# SHASwitchOutput.net
KiCad netlist of a schematic drawn in EAGLE
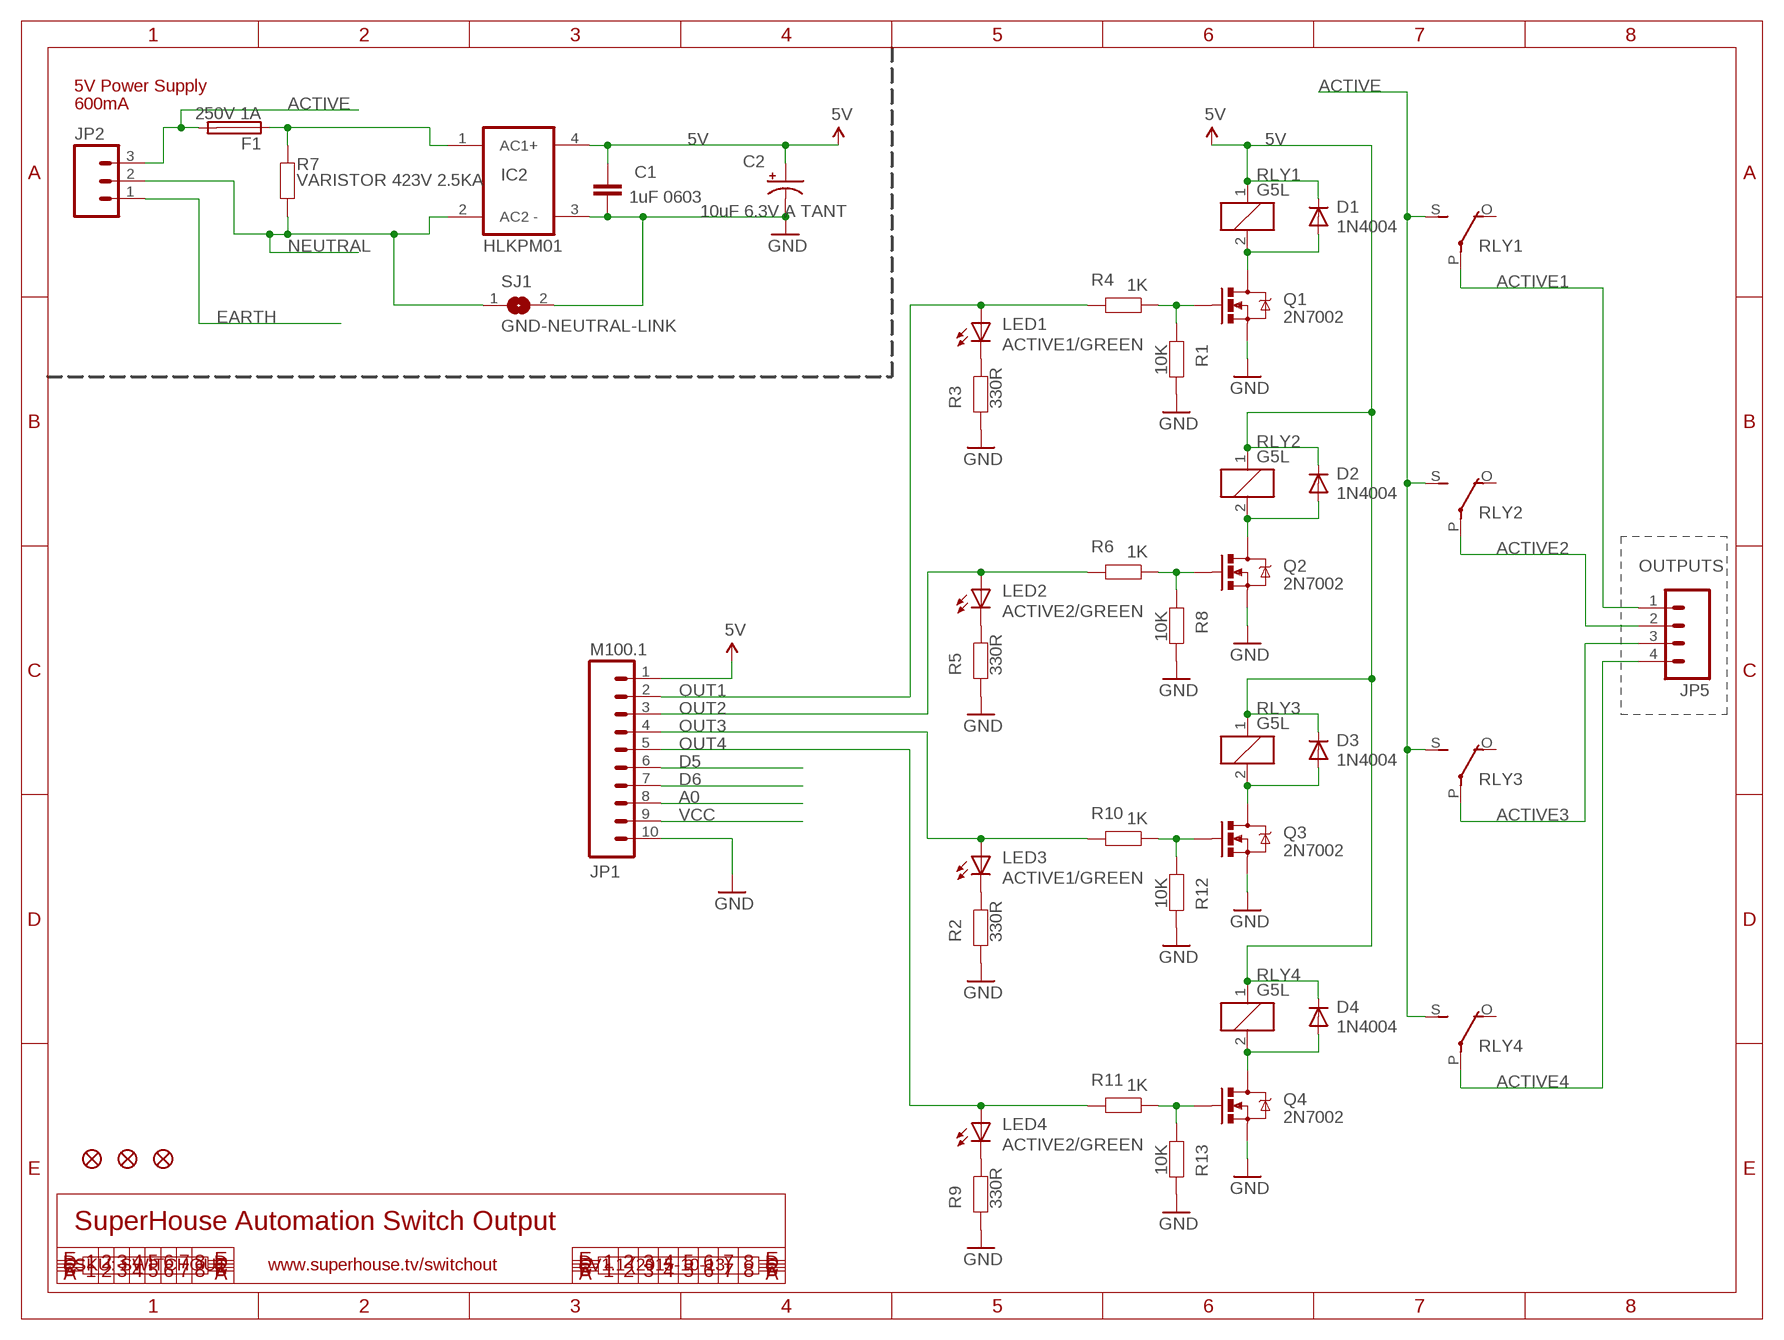
[diagram p0: schematic, sheet 1]

(export (version "E")
  (design (tool "Eeschema 10.0.6"))
  (components
    (comp (ref "C1")
      (value "1uF 0603")
      (footprint "eagle-import:0603@1")
      (libsource (lib "eagle-import") (part "CAP0603"))
    )
    (comp (ref "C2")
      (value "10uF 6.3V A TANT")
      (footprint "eagle-import:EIA3216")
      (libsource (lib "eagle-import") (part "CAP_POL1206"))
    )
    (comp (ref "D1")
      (value "1N4004")
      (footprint "eagle-import:SMB-DIODE")
      (libsource (lib "eagle-import") (part "DIODESMB"))
    )
    (comp (ref "D2")
      (value "1N4004")
      (footprint "eagle-import:SMB-DIODE")
      (libsource (lib "eagle-import") (part "DIODESMB"))
    )
    (comp (ref "D3")
      (value "1N4004")
      (footprint "eagle-import:SMB-DIODE")
      (libsource (lib "eagle-import") (part "DIODESMB"))
    )
    (comp (ref "D4")
      (value "1N4004")
      (footprint "eagle-import:SMB-DIODE")
      (libsource (lib "eagle-import") (part "DIODESMB"))
    )
    (comp (ref "F1")
      (value "250V 1A")
      (footprint "eagle-import:PICOFUSE-V")
      (libsource (lib "eagle-import") (part "PICOFUSEV"))
    )
    (comp (ref "FID1")
      (value "FIDUCIAL1X2.5")
      (footprint "eagle-import:FIDUCIAL-1X2.5")
      (libsource (lib "eagle-import") (part "FIDUCIAL1X2.5"))
    )
    (comp (ref "FID2")
      (value "FIDUCIAL1X2.5")
      (footprint "eagle-import:FIDUCIAL-1X2.5")
      (libsource (lib "eagle-import") (part "FIDUCIAL1X2.5"))
    )
    (comp (ref "FID3")
      (value "FIDUCIAL1X2.5")
      (footprint "eagle-import:FIDUCIAL-1X2.5")
      (libsource (lib "eagle-import") (part "FIDUCIAL1X2.5"))
    )
    (comp (ref "IC2")
      (value "HLKPM01")
      (footprint "eagle-import:HLKPM01")
      (libsource (lib "eagle-import") (part "HLKPM01"))
    )
    (comp (ref "JP1")
      (value "M100.1")
      (footprint "eagle-import:1X10")
      (libsource (lib "eagle-import") (part "M100.1"))
    )
    (comp (ref "JP2")
      (value "M035MM")
      (footprint "eagle-import:SCREWTERMINAL-5MM-3")
      (libsource (lib "eagle-import") (part "M035MM"))
    )
    (comp (ref "JP5")
      (value "M045MM")
      (footprint "eagle-import:SCREWTERMINAL-5MM-4")
      (libsource (lib "eagle-import") (part "M045MM"))
    )
    (comp (ref "LED1")
      (value "ACTIVE1/GREEN")
      (footprint "eagle-import:LED-0603")
      (libsource (lib "eagle-import") (part "LED0603"))
    )
    (comp (ref "LED2")
      (value "ACTIVE2/GREEN")
      (footprint "eagle-import:LED-0603")
      (libsource (lib "eagle-import") (part "LED0603"))
    )
    (comp (ref "LED3")
      (value "ACTIVE1/GREEN")
      (footprint "eagle-import:LED-0603")
      (libsource (lib "eagle-import") (part "LED0603"))
    )
    (comp (ref "LED4")
      (value "ACTIVE2/GREEN")
      (footprint "eagle-import:LED-0603")
      (libsource (lib "eagle-import") (part "LED0603"))
    )
    (comp (ref "Q1")
      (value "2N7002")
      (footprint "eagle-import:SOT23-3")
      (libsource (lib "eagle-import") (part "MOSFET-NCHANNELSMD"))
    )
    (comp (ref "Q2")
      (value "2N7002")
      (footprint "eagle-import:SOT23-3")
      (libsource (lib "eagle-import") (part "MOSFET-NCHANNELSMD"))
    )
    (comp (ref "Q3")
      (value "2N7002")
      (footprint "eagle-import:SOT23-3")
      (libsource (lib "eagle-import") (part "MOSFET-NCHANNELSMD"))
    )
    (comp (ref "Q4")
      (value "2N7002")
      (footprint "eagle-import:SOT23-3")
      (libsource (lib "eagle-import") (part "MOSFET-NCHANNELSMD"))
    )
    (comp (ref "R1")
      (value "10K")
      (footprint "eagle-import:0603")
      (libsource (lib "eagle-import") (part "RESISTOR0603"))
    )
    (comp (ref "R2")
      (value "330R")
      (footprint "eagle-import:0603")
      (libsource (lib "eagle-import") (part "RESISTOR0603"))
    )
    (comp (ref "R3")
      (value "330R")
      (footprint "eagle-import:0603")
      (libsource (lib "eagle-import") (part "RESISTOR0603"))
    )
    (comp (ref "R4")
      (value "1K")
      (footprint "eagle-import:0603")
      (libsource (lib "eagle-import") (part "RESISTOR0603"))
    )
    (comp (ref "R5")
      (value "330R")
      (footprint "eagle-import:0603")
      (libsource (lib "eagle-import") (part "RESISTOR0603"))
    )
    (comp (ref "R6")
      (value "1K")
      (footprint "eagle-import:0603")
      (libsource (lib "eagle-import") (part "RESISTOR0603"))
    )
    (comp (ref "R7")
      (value "VARISTOR 423V 2.5KA")
      (footprint "eagle-import:AXIAL-0.3")
      (libsource (lib "eagle-import") (part "freetronics-master-v1.1_RESISTORPTH1"))
    )
    (comp (ref "R8")
      (value "10K")
      (footprint "eagle-import:0603")
      (libsource (lib "eagle-import") (part "RESISTOR0603"))
    )
    (comp (ref "R9")
      (value "330R")
      (footprint "eagle-import:0603")
      (libsource (lib "eagle-import") (part "RESISTOR0603"))
    )
    (comp (ref "R10")
      (value "1K")
      (footprint "eagle-import:0603")
      (libsource (lib "eagle-import") (part "RESISTOR0603"))
    )
    (comp (ref "R11")
      (value "1K")
      (footprint "eagle-import:0603")
      (libsource (lib "eagle-import") (part "RESISTOR0603"))
    )
    (comp (ref "R12")
      (value "10K")
      (footprint "eagle-import:0603")
      (libsource (lib "eagle-import") (part "RESISTOR0603"))
    )
    (comp (ref "R13")
      (value "10K")
      (footprint "eagle-import:0603")
      (libsource (lib "eagle-import") (part "RESISTOR0603"))
    )
    (comp (ref "RLY1")
      (value "G5L")
      (footprint "eagle-import:G5LE")
      (libsource (lib "eagle-import") (part "G5L"))
    )
    (comp (ref "RLY2")
      (value "G5L")
      (footprint "eagle-import:G5LE")
      (libsource (lib "eagle-import") (part "G5L"))
    )
    (comp (ref "RLY3")
      (value "G5L")
      (footprint "eagle-import:G5LE")
      (libsource (lib "eagle-import") (part "G5L"))
    )
    (comp (ref "RLY4")
      (value "G5L")
      (footprint "eagle-import:G5LE")
      (libsource (lib "eagle-import") (part "G5L"))
    )
    (comp (ref "SJ1")
      (value "GND-NEUTRAL-LINK")
      (footprint "eagle-import:SJ")
      (libsource (lib "eagle-import") (part "SJN"))
    )
  )
  (nets
    (net (code "1") (name "/A0") (class "Default")
      (node (ref "JP1") (pin "8") (pinfunction "8_8") (pintype "passive"))
    )
    (net (code "2") (name "/ACTIVE") (class "Default")
      (node (ref "F1") (pin "2") (pinfunction "2_2") (pintype "passive"))
      (node (ref "JP2") (pin "3") (pinfunction "3_3") (pintype "passive"))
      (node (ref "RLY1") (pin "S") (pinfunction "S_S") (pintype "passive"))
      (node (ref "RLY2") (pin "S") (pinfunction "S_S") (pintype "passive"))
      (node (ref "RLY3") (pin "S") (pinfunction "S_S") (pintype "passive"))
      (node (ref "RLY4") (pin "S") (pinfunction "S_S") (pintype "passive"))
    )
    (net (code "3") (name "/ACTIVE1") (class "Default")
      (node (ref "JP5") (pin "1") (pinfunction "1_1") (pintype "passive"))
      (node (ref "RLY1") (pin "P") (pinfunction "P_P") (pintype "passive"))
    )
    (net (code "4") (name "/ACTIVE2") (class "Default")
      (node (ref "JP5") (pin "2") (pinfunction "2_2") (pintype "passive"))
      (node (ref "RLY2") (pin "P") (pinfunction "P_P") (pintype "passive"))
    )
    (net (code "5") (name "/ACTIVE3") (class "Default")
      (node (ref "JP5") (pin "3") (pinfunction "3_3") (pintype "passive"))
      (node (ref "RLY3") (pin "P") (pinfunction "P_P") (pintype "passive"))
    )
    (net (code "6") (name "/ACTIVE4") (class "Default")
      (node (ref "JP5") (pin "4") (pinfunction "4_4") (pintype "passive"))
      (node (ref "RLY4") (pin "P") (pinfunction "P_P") (pintype "passive"))
    )
    (net (code "7") (name "/D5") (class "Default")
      (node (ref "JP1") (pin "6") (pinfunction "6_6") (pintype "passive"))
    )
    (net (code "8") (name "/D6") (class "Default")
      (node (ref "JP1") (pin "7") (pinfunction "7_7") (pintype "passive"))
    )
    (net (code "9") (name "/EARTH") (class "Default")
      (node (ref "JP2") (pin "1") (pinfunction "1_1") (pintype "passive"))
    )
    (net (code "10") (name "/NEUTRAL") (class "Default")
      (node (ref "IC2") (pin "2") (pinfunction "AC2_2") (pintype "bidirectional"))
      (node (ref "JP2") (pin "2") (pinfunction "2_2") (pintype "passive"))
      (node (ref "R7") (pin "P$1") (pinfunction "1_P$1") (pintype "passive"))
      (node (ref "SJ1") (pin "1") (pinfunction "1_1") (pintype "passive"))
    )
    (net (code "11") (name "/OUT1") (class "Default")
      (node (ref "JP1") (pin "2") (pinfunction "2_2") (pintype "passive"))
      (node (ref "LED1") (pin "A") (pinfunction "A_A") (pintype "passive"))
      (node (ref "R4") (pin "2") (pinfunction "2_2") (pintype "passive"))
    )
    (net (code "12") (name "/OUT2") (class "Default")
      (node (ref "JP1") (pin "3") (pinfunction "3_3") (pintype "passive"))
      (node (ref "LED2") (pin "A") (pinfunction "A_A") (pintype "passive"))
      (node (ref "R6") (pin "2") (pinfunction "2_2") (pintype "passive"))
    )
    (net (code "13") (name "/OUT3") (class "Default")
      (node (ref "JP1") (pin "4") (pinfunction "4_4") (pintype "passive"))
      (node (ref "LED3") (pin "A") (pinfunction "A_A") (pintype "passive"))
      (node (ref "R10") (pin "2") (pinfunction "2_2") (pintype "passive"))
    )
    (net (code "14") (name "/OUT4") (class "Default")
      (node (ref "JP1") (pin "5") (pinfunction "5_5") (pintype "passive"))
      (node (ref "LED4") (pin "A") (pinfunction "A_A") (pintype "passive"))
      (node (ref "R11") (pin "2") (pinfunction "2_2") (pintype "passive"))
    )
    (net (code "15") (name "/VCC") (class "Default")
      (node (ref "JP1") (pin "9") (pinfunction "9_9") (pintype "passive"))
    )
    (net (code "16") (name "5V") (class "Default")
      (node (ref "C1") (pin "1") (pinfunction "1_1") (pintype "passive"))
      (node (ref "C2") (pin "A") (pinfunction "+_A") (pintype "passive"))
      (node (ref "D1") (pin "C") (pinfunction "C_C") (pintype "passive"))
      (node (ref "D2") (pin "C") (pinfunction "C_C") (pintype "passive"))
      (node (ref "D3") (pin "C") (pinfunction "C_C") (pintype "passive"))
      (node (ref "D4") (pin "C") (pinfunction "C_C") (pintype "passive"))
      (node (ref "IC2") (pin "4") (pinfunction "+_4") (pintype "bidirectional"))
      (node (ref "JP1") (pin "1") (pinfunction "1_1") (pintype "passive"))
      (node (ref "RLY1") (pin "1") (pinfunction "1_1") (pintype "passive"))
      (node (ref "RLY2") (pin "1") (pinfunction "1_1") (pintype "passive"))
      (node (ref "RLY3") (pin "1") (pinfunction "1_1") (pintype "passive"))
      (node (ref "RLY4") (pin "1") (pinfunction "1_1") (pintype "passive"))
    )
    (net (code "17") (name "GND") (class "Default")
      (node (ref "C1") (pin "2") (pinfunction "2_2") (pintype "passive"))
      (node (ref "C2") (pin "C") (pinfunction "-_C") (pintype "passive"))
      (node (ref "IC2") (pin "3") (pinfunction "-_3") (pintype "bidirectional"))
      (node (ref "JP1") (pin "10") (pinfunction "10_10") (pintype "passive"))
      (node (ref "Q1") (pin "2") (pinfunction "S_2") (pintype "passive"))
      (node (ref "Q2") (pin "2") (pinfunction "S_2") (pintype "passive"))
      (node (ref "Q3") (pin "2") (pinfunction "S_2") (pintype "passive"))
      (node (ref "Q4") (pin "2") (pinfunction "S_2") (pintype "passive"))
      (node (ref "R1") (pin "2") (pinfunction "2_2") (pintype "passive"))
      (node (ref "R12") (pin "2") (pinfunction "2_2") (pintype "passive"))
      (node (ref "R13") (pin "2") (pinfunction "2_2") (pintype "passive"))
      (node (ref "R2") (pin "1") (pinfunction "1_1") (pintype "passive"))
      (node (ref "R3") (pin "1") (pinfunction "1_1") (pintype "passive"))
      (node (ref "R5") (pin "1") (pinfunction "1_1") (pintype "passive"))
      (node (ref "R8") (pin "2") (pinfunction "2_2") (pintype "passive"))
      (node (ref "R9") (pin "1") (pinfunction "1_1") (pintype "passive"))
      (node (ref "SJ1") (pin "2") (pinfunction "2_2") (pintype "passive"))
    )
    (net (code "18") (name "Net-(IC2-AC1)") (class "Default")
      (node (ref "F1") (pin "1") (pinfunction "1_1") (pintype "passive"))
      (node (ref "IC2") (pin "1") (pinfunction "AC1_1") (pintype "bidirectional"))
      (node (ref "R7") (pin "P$2") (pinfunction "2_P$2") (pintype "passive"))
    )
    (net (code "19") (name "Net-(LED1-PadC)") (class "Default")
      (node (ref "LED1") (pin "C") (pinfunction "C_C") (pintype "passive"))
      (node (ref "R3") (pin "2") (pinfunction "2_2") (pintype "passive"))
    )
    (net (code "20") (name "Net-(LED2-PadC)") (class "Default")
      (node (ref "LED2") (pin "C") (pinfunction "C_C") (pintype "passive"))
      (node (ref "R5") (pin "2") (pinfunction "2_2") (pintype "passive"))
    )
    (net (code "21") (name "Net-(LED3-PadC)") (class "Default")
      (node (ref "LED3") (pin "C") (pinfunction "C_C") (pintype "passive"))
      (node (ref "R2") (pin "2") (pinfunction "2_2") (pintype "passive"))
    )
    (net (code "22") (name "Net-(LED4-PadC)") (class "Default")
      (node (ref "LED4") (pin "C") (pinfunction "C_C") (pintype "passive"))
      (node (ref "R9") (pin "2") (pinfunction "2_2") (pintype "passive"))
    )
    (net (code "23") (name "Net-(Q1-D)") (class "Default")
      (node (ref "D1") (pin "A") (pinfunction "A_A") (pintype "passive"))
      (node (ref "Q1") (pin "3") (pinfunction "D_3") (pintype "passive"))
      (node (ref "RLY1") (pin "2") (pinfunction "2_2") (pintype "passive"))
    )
    (net (code "24") (name "Net-(Q1-G)") (class "Default")
      (node (ref "Q1") (pin "1") (pinfunction "G_1") (pintype "passive"))
      (node (ref "R1") (pin "1") (pinfunction "1_1") (pintype "passive"))
      (node (ref "R4") (pin "1") (pinfunction "1_1") (pintype "passive"))
    )
    (net (code "25") (name "Net-(Q2-D)") (class "Default")
      (node (ref "D2") (pin "A") (pinfunction "A_A") (pintype "passive"))
      (node (ref "Q2") (pin "3") (pinfunction "D_3") (pintype "passive"))
      (node (ref "RLY2") (pin "2") (pinfunction "2_2") (pintype "passive"))
    )
    (net (code "26") (name "Net-(Q2-G)") (class "Default")
      (node (ref "Q2") (pin "1") (pinfunction "G_1") (pintype "passive"))
      (node (ref "R6") (pin "1") (pinfunction "1_1") (pintype "passive"))
      (node (ref "R8") (pin "1") (pinfunction "1_1") (pintype "passive"))
    )
    (net (code "27") (name "Net-(Q3-D)") (class "Default")
      (node (ref "D3") (pin "A") (pinfunction "A_A") (pintype "passive"))
      (node (ref "Q3") (pin "3") (pinfunction "D_3") (pintype "passive"))
      (node (ref "RLY3") (pin "2") (pinfunction "2_2") (pintype "passive"))
    )
    (net (code "28") (name "Net-(Q3-G)") (class "Default")
      (node (ref "Q3") (pin "1") (pinfunction "G_1") (pintype "passive"))
      (node (ref "R10") (pin "1") (pinfunction "1_1") (pintype "passive"))
      (node (ref "R12") (pin "1") (pinfunction "1_1") (pintype "passive"))
    )
    (net (code "29") (name "Net-(Q4-D)") (class "Default")
      (node (ref "D4") (pin "A") (pinfunction "A_A") (pintype "passive"))
      (node (ref "Q4") (pin "3") (pinfunction "D_3") (pintype "passive"))
      (node (ref "RLY4") (pin "2") (pinfunction "2_2") (pintype "passive"))
    )
    (net (code "30") (name "Net-(Q4-G)") (class "Default")
      (node (ref "Q4") (pin "1") (pinfunction "G_1") (pintype "passive"))
      (node (ref "R11") (pin "1") (pinfunction "1_1") (pintype "passive"))
      (node (ref "R13") (pin "1") (pinfunction "1_1") (pintype "passive"))
    )
    (net (code "31") (name "unconnected-(RLY1-PadO)") (class "Default")
      (node (ref "RLY1") (pin "O") (pinfunction "O_O") (pintype "passive"))
    )
    (net (code "32") (name "unconnected-(RLY2-PadO)") (class "Default")
      (node (ref "RLY2") (pin "O") (pinfunction "O_O") (pintype "passive"))
    )
    (net (code "33") (name "unconnected-(RLY3-PadO)") (class "Default")
      (node (ref "RLY3") (pin "O") (pinfunction "O_O") (pintype "passive"))
    )
    (net (code "34") (name "unconnected-(RLY4-PadO)") (class "Default")
      (node (ref "RLY4") (pin "O") (pinfunction "O_O") (pintype "passive"))
    )
  )
)
